# royer.net
KiCad netlist of a schematic drawn in EAGLE
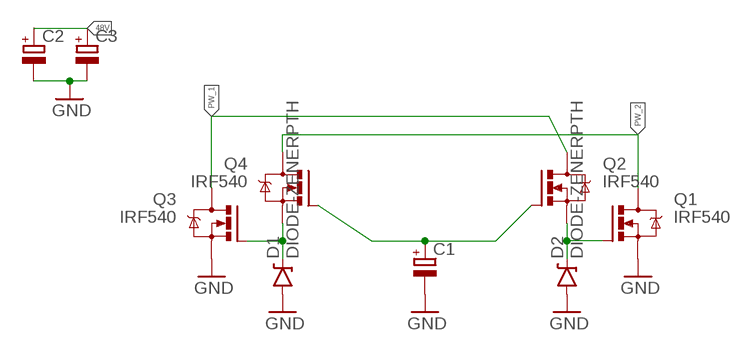
[diagram p0: schematic, sheet 1]

(export (version "E")
  (design (tool "Eeschema 10.0.6"))
  (components
    (comp (ref "C1")
      (value "CPOL-EUSANYO_C")
      (footprint "eagle-import:SANYO-OSCON_C")
      (libsource (lib "eagle-import") (part "CPOL-EUSANYO_C"))
    )
    (comp (ref "C2")
      (value "CPOL-EUSANYO_9F")
      (footprint "eagle-import:SANYO-OSCON_9F")
      (libsource (lib "eagle-import") (part "CPOL-EUSANYO_9F"))
    )
    (comp (ref "C3")
      (value "CPOL-EUSANYO_9F")
      (footprint "eagle-import:SANYO-OSCON_9F")
      (libsource (lib "eagle-import") (part "CPOL-EUSANYO_9F"))
    )
    (comp (ref "D1")
      (value "DIODE-ZENERPTH")
      (footprint "eagle-import:DIODE-ZENER")
      (libsource (lib "eagle-import") (part "DIODE-ZENERPTH"))
    )
    (comp (ref "D2")
      (value "DIODE-ZENERPTH")
      (footprint "eagle-import:DIODE-ZENER")
      (libsource (lib "eagle-import") (part "DIODE-ZENERPTH"))
    )
    (comp (ref "Q1")
      (value "IRF540")
      (footprint "eagle-import:TO220BV")
      (libsource (lib "eagle-import") (part "IRF540"))
    )
    (comp (ref "Q2")
      (value "IRF540")
      (footprint "eagle-import:TO220BV")
      (libsource (lib "eagle-import") (part "IRF540"))
    )
    (comp (ref "Q3")
      (value "IRF540")
      (footprint "eagle-import:TO220BV")
      (libsource (lib "eagle-import") (part "IRF540"))
    )
    (comp (ref "Q4")
      (value "IRF540")
      (footprint "eagle-import:TO220BV")
      (libsource (lib "eagle-import") (part "IRF540"))
    )
  )
  (nets
    (net (code "1") (name "48V") (class "Default")
      (node (ref "C2") (pin "+") (pinfunction "+_+") (pintype "passive"))
      (node (ref "C3") (pin "+") (pinfunction "+_+") (pintype "passive"))
    )
    (net (code "2") (name "GND") (class "Default")
      (node (ref "C1") (pin "-") (pinfunction "-_-") (pintype "passive"))
      (node (ref "C2") (pin "-") (pinfunction "-_-") (pintype "passive"))
      (node (ref "C3") (pin "-") (pinfunction "-_-") (pintype "passive"))
      (node (ref "D1") (pin "P$2") (pinfunction "A_P$2") (pintype "passive"))
      (node (ref "D2") (pin "P$2") (pinfunction "A_P$2") (pintype "passive"))
      (node (ref "Q1") (pin "S") (pinfunction "S_S") (pintype "passive"))
      (node (ref "Q3") (pin "S") (pinfunction "S_S") (pintype "passive"))
    )
    (net (code "3") (name "Net-(C1-Pad+)") (class "Default")
      (node (ref "C1") (pin "+") (pinfunction "+_+") (pintype "passive"))
      (node (ref "Q2") (pin "G") (pinfunction "G_G") (pintype "passive"))
      (node (ref "Q4") (pin "G") (pinfunction "G_G") (pintype "passive"))
    )
    (net (code "4") (name "Net-(D1-C)") (class "Default")
      (node (ref "D1") (pin "P$1") (pinfunction "C_P$1") (pintype "passive"))
      (node (ref "Q3") (pin "G") (pinfunction "G_G") (pintype "passive"))
      (node (ref "Q4") (pin "S") (pinfunction "S_S") (pintype "passive"))
    )
    (net (code "5") (name "Net-(D2-C)") (class "Default")
      (node (ref "D2") (pin "P$1") (pinfunction "C_P$1") (pintype "passive"))
      (node (ref "Q1") (pin "G") (pinfunction "G_G") (pintype "passive"))
      (node (ref "Q2") (pin "S") (pinfunction "S_S") (pintype "passive"))
    )
    (net (code "6") (name "PW_1") (class "Default")
      (node (ref "Q2") (pin "D") (pinfunction "D_D") (pintype "passive"))
      (node (ref "Q3") (pin "D") (pinfunction "D_D") (pintype "passive"))
    )
    (net (code "7") (name "PW_2") (class "Default")
      (node (ref "Q1") (pin "D") (pinfunction "D_D") (pintype "passive"))
      (node (ref "Q4") (pin "D") (pinfunction "D_D") (pintype "passive"))
    )
  )
)
